# ads1115.net
KiCad netlist of a schematic drawn in EAGLE
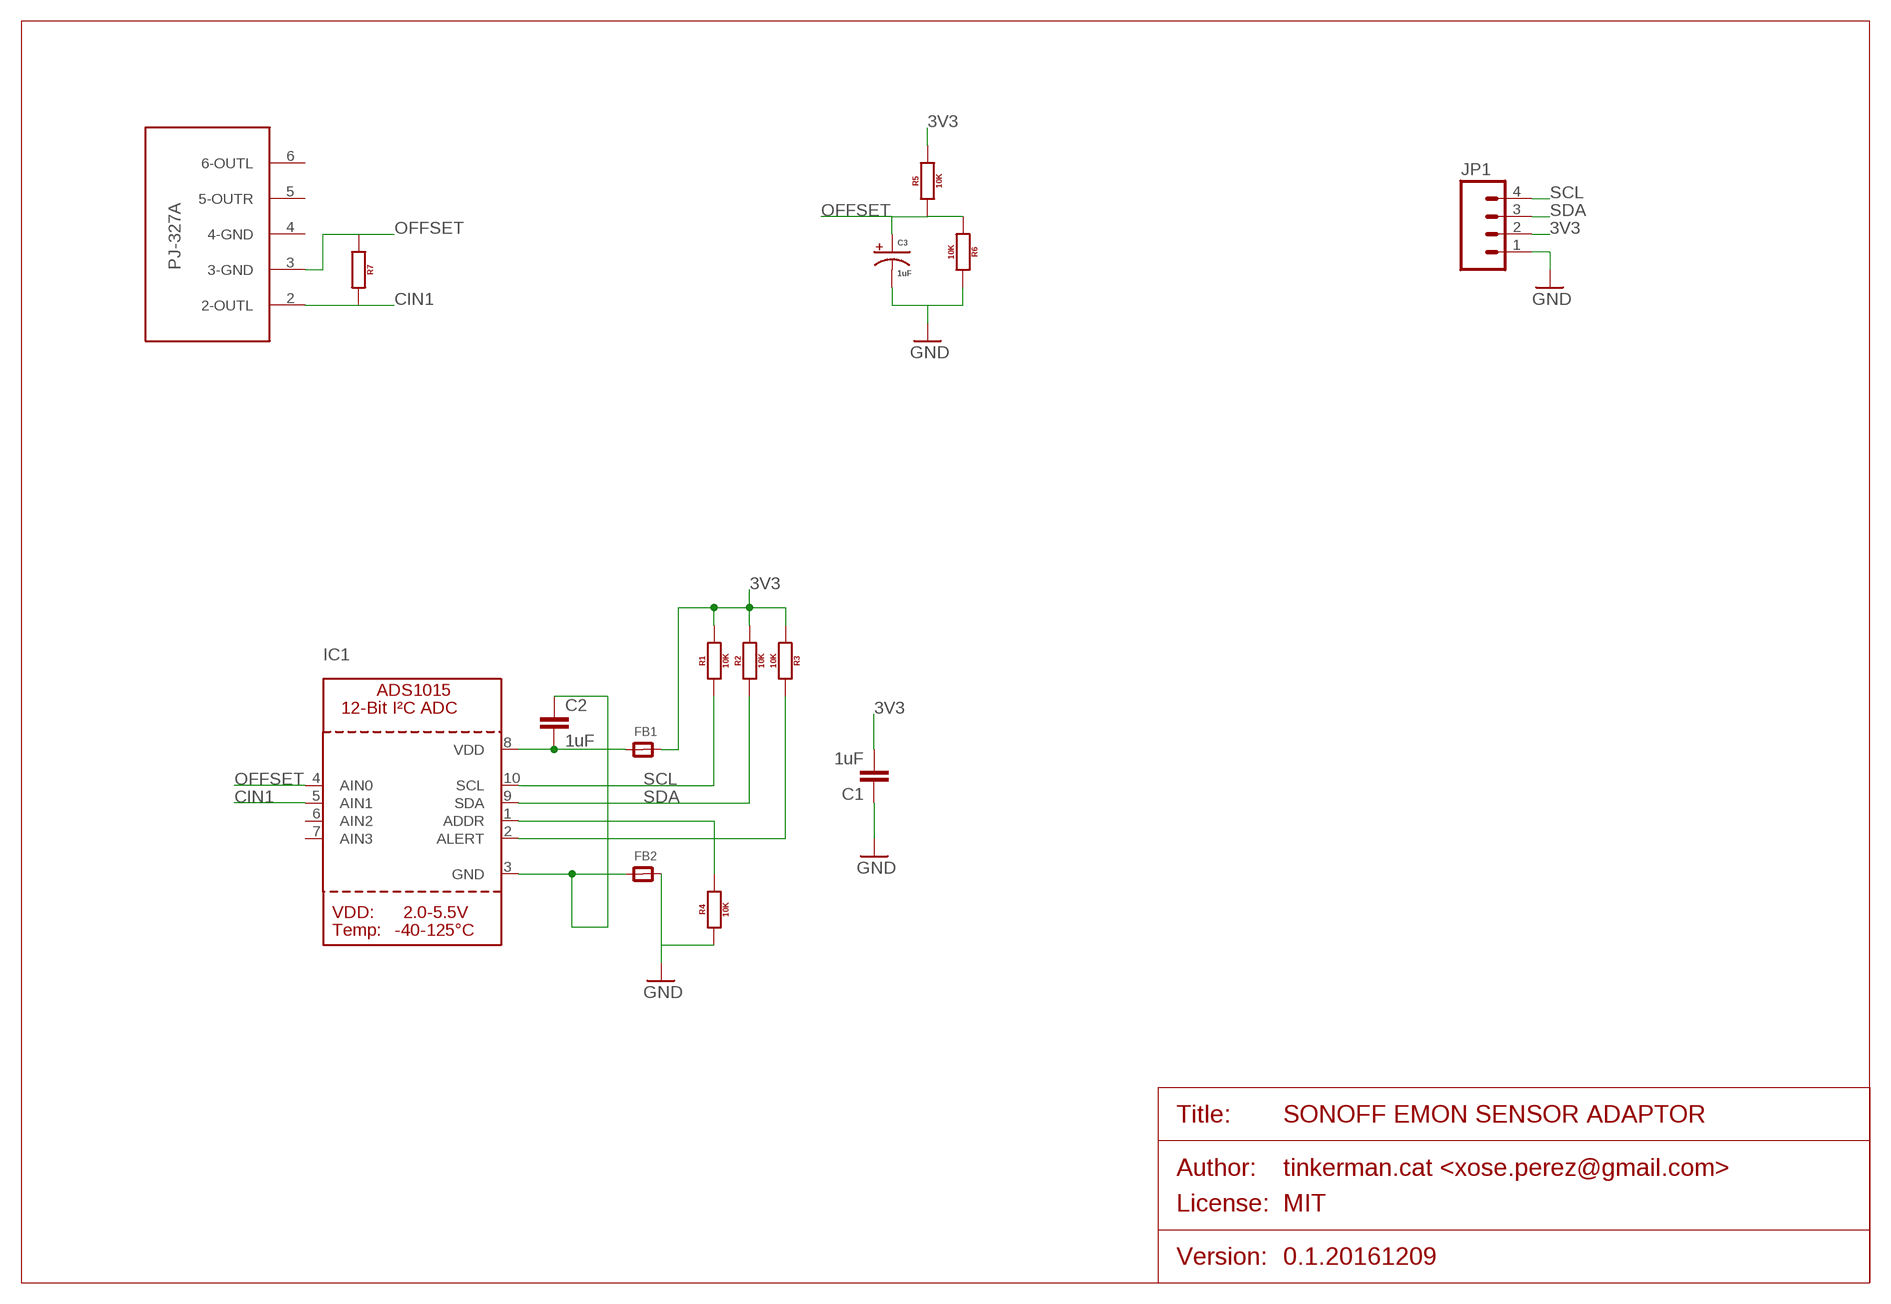
[diagram p0: schematic, sheet 1]

(export (version "E")
  (design (tool "Eeschema 10.0.6"))
  (components
    (comp (ref "C1")
      (value "1uF")
      (footprint "eagle-import:0805")
      (libsource (lib "eagle-import") (part "C-EU0805"))
    )
    (comp (ref "C2")
      (value "1uF")
      (footprint "eagle-import:0805")
      (libsource (lib "eagle-import") (part "C-EU0805"))
    )
    (comp (ref "C3")
      (value "1uF")
      (footprint "eagle-import:PANASONIC_C")
      (libsource (lib "eagle-import") (part "CAP_POLC"))
    )
    (comp (ref "CURR1")
      (value "PJ-327A")
      (footprint "eagle-import:PJ-327A")
      (libsource (lib "eagle-import") (part "PJ-327A"))
    )
    (comp (ref "FB1")
      (value "FERRITE_0805MP")
      (footprint "eagle-import:_0805MP")
      (libsource (lib "eagle-import") (part "FERRITE_0805MP"))
    )
    (comp (ref "FB2")
      (value "FERRITE_0805MP")
      (footprint "eagle-import:_0805MP")
      (libsource (lib "eagle-import") (part "FERRITE_0805MP"))
    )
    (comp (ref "IC1")
      (value "ADC_ADS1015")
      (footprint "eagle-import:MSOP10")
      (libsource (lib "eagle-import") (part "ADC_ADS1015"))
    )
    (comp (ref "JP1")
      (value "M04PTH")
      (footprint "eagle-import:1X04")
      (libsource (lib "eagle-import") (part "M04PTH"))
    )
    (comp (ref "R1")
      (value "10K")
      (footprint "eagle-import:0805")
      (libsource (lib "eagle-import") (part "RESISTOR0805"))
    )
    (comp (ref "R2")
      (value "10K")
      (footprint "eagle-import:0805")
      (libsource (lib "eagle-import") (part "RESISTOR0805"))
    )
    (comp (ref "R3")
      (value "10K")
      (footprint "eagle-import:0805")
      (libsource (lib "eagle-import") (part "RESISTOR0805"))
    )
    (comp (ref "R4")
      (value "10K")
      (footprint "eagle-import:0805")
      (libsource (lib "eagle-import") (part "RESISTOR0805"))
    )
    (comp (ref "R5")
      (value "10K")
      (footprint "eagle-import:0805")
      (libsource (lib "eagle-import") (part "RESISTOR0805"))
    )
    (comp (ref "R6")
      (value "10K")
      (footprint "eagle-import:0805")
      (libsource (lib "eagle-import") (part "RESISTOR0805"))
    )
    (comp (ref "R7")
      (value "RESISTOR0805")
      (footprint "eagle-import:0805")
      (libsource (lib "eagle-import") (part "RESISTOR0805"))
    )
  )
  (nets
    (net (code "1") (name "/3V3") (class "Default")
      (node (ref "C1") (pin "2") (pinfunction "2_2") (pintype "passive"))
      (node (ref "FB1") (pin "2") (pinfunction "P$2_2") (pintype "passive"))
      (node (ref "JP1") (pin "2") (pinfunction "2_2") (pintype "passive"))
      (node (ref "R1") (pin "2") (pinfunction "2_2") (pintype "passive"))
      (node (ref "R2") (pin "2") (pinfunction "2_2") (pintype "passive"))
      (node (ref "R3") (pin "1") (pinfunction "1_1") (pintype "passive"))
      (node (ref "R5") (pin "2") (pinfunction "2_2") (pintype "passive"))
    )
    (net (code "2") (name "/CIN1") (class "Default")
      (node (ref "CURR1") (pin "2") (pinfunction "2-OUTL_2") (pintype "bidirectional"))
      (node (ref "IC1") (pin "5") (pinfunction "AIN1_5") (pintype "bidirectional"))
      (node (ref "R7") (pin "2") (pinfunction "2_2") (pintype "passive"))
    )
    (net (code "3") (name "/OFFSET") (class "Default")
      (node (ref "C3") (pin "+") (pinfunction "+_+") (pintype "passive"))
      (node (ref "CURR1") (pin "3") (pinfunction "3-GND_3") (pintype "bidirectional"))
      (node (ref "IC1") (pin "4") (pinfunction "AIN0_4") (pintype "bidirectional"))
      (node (ref "R5") (pin "1") (pinfunction "1_1") (pintype "passive"))
      (node (ref "R6") (pin "1") (pinfunction "1_1") (pintype "passive"))
      (node (ref "R7") (pin "1") (pinfunction "1_1") (pintype "passive"))
    )
    (net (code "4") (name "/SCL") (class "Default")
      (node (ref "IC1") (pin "10") (pinfunction "SCL_10") (pintype "bidirectional"))
      (node (ref "JP1") (pin "4") (pinfunction "4_4") (pintype "passive"))
      (node (ref "R1") (pin "1") (pinfunction "1_1") (pintype "passive"))
    )
    (net (code "5") (name "/SDA") (class "Default")
      (node (ref "IC1") (pin "9") (pinfunction "SDA_9") (pintype "bidirectional"))
      (node (ref "JP1") (pin "3") (pinfunction "3_3") (pintype "passive"))
      (node (ref "R2") (pin "1") (pinfunction "1_1") (pintype "passive"))
    )
    (net (code "6") (name "GND") (class "Default")
      (node (ref "C1") (pin "1") (pinfunction "1_1") (pintype "passive"))
      (node (ref "C3") (pin "-") (pinfunction "-_-") (pintype "passive"))
      (node (ref "FB2") (pin "2") (pinfunction "P$2_2") (pintype "passive"))
      (node (ref "JP1") (pin "1") (pinfunction "1_1") (pintype "passive"))
      (node (ref "R4") (pin "1") (pinfunction "1_1") (pintype "passive"))
      (node (ref "R6") (pin "2") (pinfunction "2_2") (pintype "passive"))
    )
    (net (code "7") (name "Net-(FB1-P$1)") (class "Default")
      (node (ref "C2") (pin "2") (pinfunction "2_2") (pintype "passive"))
      (node (ref "FB1") (pin "1") (pinfunction "P$1_1") (pintype "passive"))
      (node (ref "IC1") (pin "8") (pinfunction "VDD_8") (pintype "bidirectional"))
    )
    (net (code "8") (name "Net-(FB2-P$1)") (class "Default")
      (node (ref "C2") (pin "1") (pinfunction "1_1") (pintype "passive"))
      (node (ref "FB2") (pin "1") (pinfunction "P$1_1") (pintype "passive"))
      (node (ref "IC1") (pin "3") (pinfunction "GND_3") (pintype "bidirectional"))
    )
    (net (code "9") (name "Net-(IC1-ADDR)") (class "Default")
      (node (ref "IC1") (pin "1") (pinfunction "ADDR_1") (pintype "bidirectional"))
      (node (ref "R4") (pin "2") (pinfunction "2_2") (pintype "passive"))
    )
    (net (code "10") (name "Net-(IC1-ALERT)") (class "Default")
      (node (ref "IC1") (pin "2") (pinfunction "ALERT_2") (pintype "bidirectional"))
      (node (ref "R3") (pin "2") (pinfunction "2_2") (pintype "passive"))
    )
    (net (code "11") (name "unconnected-(CURR1-4-GND-Pad4)") (class "Default")
      (node (ref "CURR1") (pin "4") (pinfunction "4-GND_4") (pintype "bidirectional"))
    )
    (net (code "12") (name "unconnected-(CURR1-5-OUTR-Pad5)") (class "Default")
      (node (ref "CURR1") (pin "5") (pinfunction "5-OUTR_5") (pintype "bidirectional"))
    )
    (net (code "13") (name "unconnected-(CURR1-6-OUTL-Pad6)") (class "Default")
      (node (ref "CURR1") (pin "6") (pinfunction "6-OUTL_6") (pintype "bidirectional"))
    )
    (net (code "14") (name "unconnected-(IC1-AIN2-Pad6)") (class "Default")
      (node (ref "IC1") (pin "6") (pinfunction "AIN2_6") (pintype "bidirectional"))
    )
    (net (code "15") (name "unconnected-(IC1-AIN3-Pad7)") (class "Default")
      (node (ref "IC1") (pin "7") (pinfunction "AIN3_7") (pintype "bidirectional"))
    )
  )
)
